# ChannelOutput.net
KiCad netlist of a schematic drawn in EAGLE
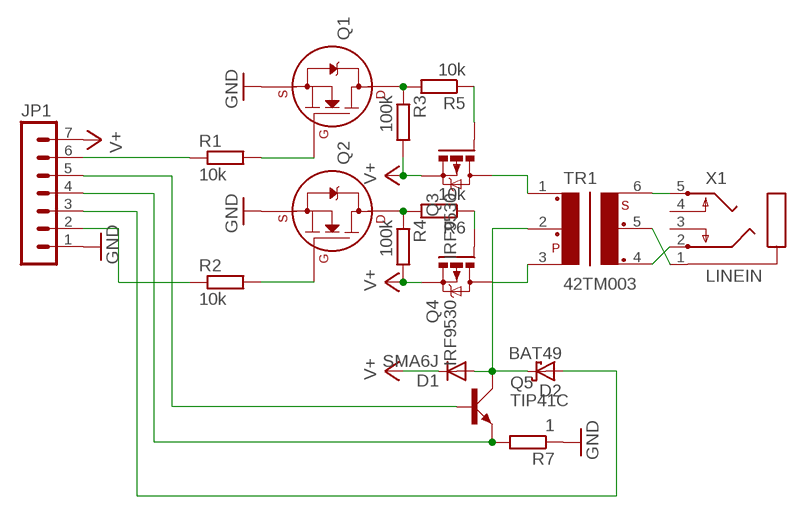
[diagram p0: schematic, sheet 1]

(export (version "E")
  (design (tool "Eeschema 10.0.6"))
  (components
    (comp (ref "D1")
      (value "SMA6J")
      (footprint "eagle-import:DO41-10")
      (libsource (lib "eagle-import") (part "1N4004"))
    )
    (comp (ref "D2")
      (value "BAT49")
      (footprint "eagle-import:DO41-10")
      (libsource (lib "eagle-import") (part "BAT49"))
    )
    (comp (ref "JP1")
      (value "MA07-1")
      (footprint "eagle-import:MA07-1")
      (libsource (lib "eagle-import") (part "MA07-1"))
    )
    (comp (ref "Q1")
      (value "2N7000_TO92")
      (footprint "eagle-import:TO-92")
      (libsource (lib "eagle-import") (part "2N700_TO920"))
    )
    (comp (ref "Q2")
      (value "2N7000_TO92")
      (footprint "eagle-import:TO-92")
      (libsource (lib "eagle-import") (part "2N700_TO920"))
    )
    (comp (ref "Q3")
      (value "IRF9530")
      (footprint "eagle-import:TO220BV")
      (libsource (lib "eagle-import") (part "IRF9530"))
    )
    (comp (ref "Q4")
      (value "IRF9530")
      (footprint "eagle-import:TO220BV")
      (libsource (lib "eagle-import") (part "IRF9530"))
    )
    (comp (ref "Q5")
      (value "TIP41C")
      (footprint "eagle-import:TO220AV")
      (libsource (lib "eagle-import") (part "TIP41C"))
    )
    (comp (ref "R1")
      (value "10k")
      (footprint "eagle-import:0207_2V")
      (libsource (lib "eagle-import") (part "R-EU_0207/2V"))
    )
    (comp (ref "R2")
      (value "10k")
      (footprint "eagle-import:0207_2V")
      (libsource (lib "eagle-import") (part "R-EU_0207/2V"))
    )
    (comp (ref "R3")
      (value "100k")
      (footprint "eagle-import:0204_5")
      (libsource (lib "eagle-import") (part "R-EU_0204/5"))
    )
    (comp (ref "R4")
      (value "100k")
      (footprint "eagle-import:0204_5")
      (libsource (lib "eagle-import") (part "R-EU_0204/5"))
    )
    (comp (ref "R5")
      (value "10k")
      (footprint "eagle-import:0207_2V")
      (libsource (lib "eagle-import") (part "R-EU_0207/2V"))
    )
    (comp (ref "R6")
      (value "10k")
      (footprint "eagle-import:0207_2V")
      (libsource (lib "eagle-import") (part "R-EU_0207/2V"))
    )
    (comp (ref "R7")
      (value "1")
      (footprint "eagle-import:0207_2V")
      (libsource (lib "eagle-import") (part "R-EU_0207/2V"))
    )
    (comp (ref "TR1")
      (value "42TM003")
      (footprint "eagle-import:42TM")
      (libsource (lib "eagle-import") (part "42T?M003"))
    )
    (comp (ref "X1")
      (value "LINEIN")
      (footprint "eagle-import:PG203J")
      (libsource (lib "eagle-import") (part "PG203J"))
    )
  )
  (nets
    (net (code "1") (name "GND") (class "Default")
      (node (ref "JP1") (pin "1") (pinfunction "1_1") (pintype "passive"))
      (node (ref "Q1") (pin "1") (pinfunction "S_1") (pintype "bidirectional"))
      (node (ref "Q2") (pin "1") (pinfunction "S_1") (pintype "bidirectional"))
      (node (ref "R7") (pin "1") (pinfunction "1_1") (pintype "passive"))
    )
    (net (code "2") (name "Net-(D1-PadA)") (class "Default")
      (node (ref "D1") (pin "A") (pinfunction "A_A") (pintype "passive"))
      (node (ref "D2") (pin "C") (pinfunction "C_C") (pintype "passive"))
      (node (ref "Q5") (pin "C") (pinfunction "C_C") (pintype "passive"))
      (node (ref "TR1") (pin "2") (pinfunction "2_2") (pintype "passive"))
    )
    (net (code "3") (name "Net-(D2-PadA)") (class "Default")
      (node (ref "D2") (pin "A") (pinfunction "A_A") (pintype "passive"))
      (node (ref "JP1") (pin "3") (pinfunction "3_3") (pintype "passive"))
    )
    (net (code "4") (name "Net-(JP1-Pad2)") (class "Default")
      (node (ref "JP1") (pin "2") (pinfunction "2_2") (pintype "passive"))
      (node (ref "R2") (pin "1") (pinfunction "1_1") (pintype "passive"))
    )
    (net (code "5") (name "Net-(JP1-Pad4)") (class "Default")
      (node (ref "JP1") (pin "4") (pinfunction "4_4") (pintype "passive"))
      (node (ref "Q5") (pin "E") (pinfunction "E_E") (pintype "passive"))
      (node (ref "R7") (pin "2") (pinfunction "2_2") (pintype "passive"))
    )
    (net (code "6") (name "Net-(JP1-Pad5)") (class "Default")
      (node (ref "JP1") (pin "5") (pinfunction "5_5") (pintype "passive"))
      (node (ref "Q5") (pin "B") (pinfunction "B_B") (pintype "passive"))
    )
    (net (code "7") (name "Net-(JP1-Pad6)") (class "Default")
      (node (ref "JP1") (pin "6") (pinfunction "6_6") (pintype "passive"))
      (node (ref "R1") (pin "1") (pinfunction "1_1") (pintype "passive"))
    )
    (net (code "8") (name "Net-(Q1-D)") (class "Default")
      (node (ref "Q1") (pin "3") (pinfunction "D_3") (pintype "bidirectional"))
      (node (ref "R3") (pin "1") (pinfunction "1_1") (pintype "passive"))
      (node (ref "R5") (pin "2") (pinfunction "2_2") (pintype "passive"))
    )
    (net (code "9") (name "Net-(Q1-G)") (class "Default")
      (node (ref "Q1") (pin "2") (pinfunction "G_2") (pintype "tri_state"))
      (node (ref "R1") (pin "2") (pinfunction "2_2") (pintype "passive"))
    )
    (net (code "10") (name "Net-(Q2-D)") (class "Default")
      (node (ref "Q2") (pin "3") (pinfunction "D_3") (pintype "bidirectional"))
      (node (ref "R4") (pin "1") (pinfunction "1_1") (pintype "passive"))
      (node (ref "R6") (pin "2") (pinfunction "2_2") (pintype "passive"))
    )
    (net (code "11") (name "Net-(Q2-G)") (class "Default")
      (node (ref "Q2") (pin "2") (pinfunction "G_2") (pintype "tri_state"))
      (node (ref "R2") (pin "2") (pinfunction "2_2") (pintype "passive"))
    )
    (net (code "12") (name "Net-(Q3-PadD)") (class "Default")
      (node (ref "Q3") (pin "D") (pinfunction "D_D") (pintype "passive"))
      (node (ref "TR1") (pin "1") (pinfunction "1_1") (pintype "passive"))
    )
    (net (code "13") (name "Net-(Q3-PadG)") (class "Default")
      (node (ref "Q3") (pin "G") (pinfunction "G_G") (pintype "passive"))
      (node (ref "R5") (pin "1") (pinfunction "1_1") (pintype "passive"))
    )
    (net (code "14") (name "Net-(Q4-PadD)") (class "Default")
      (node (ref "Q4") (pin "D") (pinfunction "D_D") (pintype "passive"))
      (node (ref "TR1") (pin "3") (pinfunction "3_3") (pintype "passive"))
    )
    (net (code "15") (name "Net-(Q4-PadG)") (class "Default")
      (node (ref "Q4") (pin "G") (pinfunction "G_G") (pintype "passive"))
      (node (ref "R6") (pin "1") (pinfunction "1_1") (pintype "passive"))
    )
    (net (code "16") (name "Net-(TR1-Pad4)") (class "Default")
      (node (ref "TR1") (pin "4") (pinfunction "4_4") (pintype "passive"))
      (node (ref "X1") (pin "2") (pinfunction "2_2") (pintype "passive"))
    )
    (net (code "17") (name "Net-(TR1-Pad5)") (class "Default")
      (node (ref "TR1") (pin "5") (pinfunction "5_5") (pintype "passive"))
      (node (ref "X1") (pin "1") (pinfunction "1_1") (pintype "passive"))
    )
    (net (code "18") (name "Net-(TR1-Pad6)") (class "Default")
      (node (ref "TR1") (pin "6") (pinfunction "6_6") (pintype "passive"))
      (node (ref "X1") (pin "5") (pinfunction "5_5") (pintype "passive"))
    )
    (net (code "19") (name "V+") (class "Default")
      (node (ref "D1") (pin "C") (pinfunction "C_C") (pintype "passive"))
      (node (ref "JP1") (pin "7") (pinfunction "7_7") (pintype "passive"))
      (node (ref "Q3") (pin "S") (pinfunction "S_S") (pintype "passive"))
      (node (ref "Q4") (pin "S") (pinfunction "S_S") (pintype "passive"))
      (node (ref "R3") (pin "2") (pinfunction "2_2") (pintype "passive"))
      (node (ref "R4") (pin "2") (pinfunction "2_2") (pintype "passive"))
    )
    (net (code "20") (name "unconnected-(X1-Pad3)") (class "Default")
      (node (ref "X1") (pin "3") (pinfunction "3_3") (pintype "passive"))
    )
    (net (code "21") (name "unconnected-(X1-Pad4)") (class "Default")
      (node (ref "X1") (pin "4") (pinfunction "4_4") (pintype "passive"))
    )
  )
)
